# ManipulatorControlPartSCH.net
KiCad netlist of a schematic drawn in Altium Designer
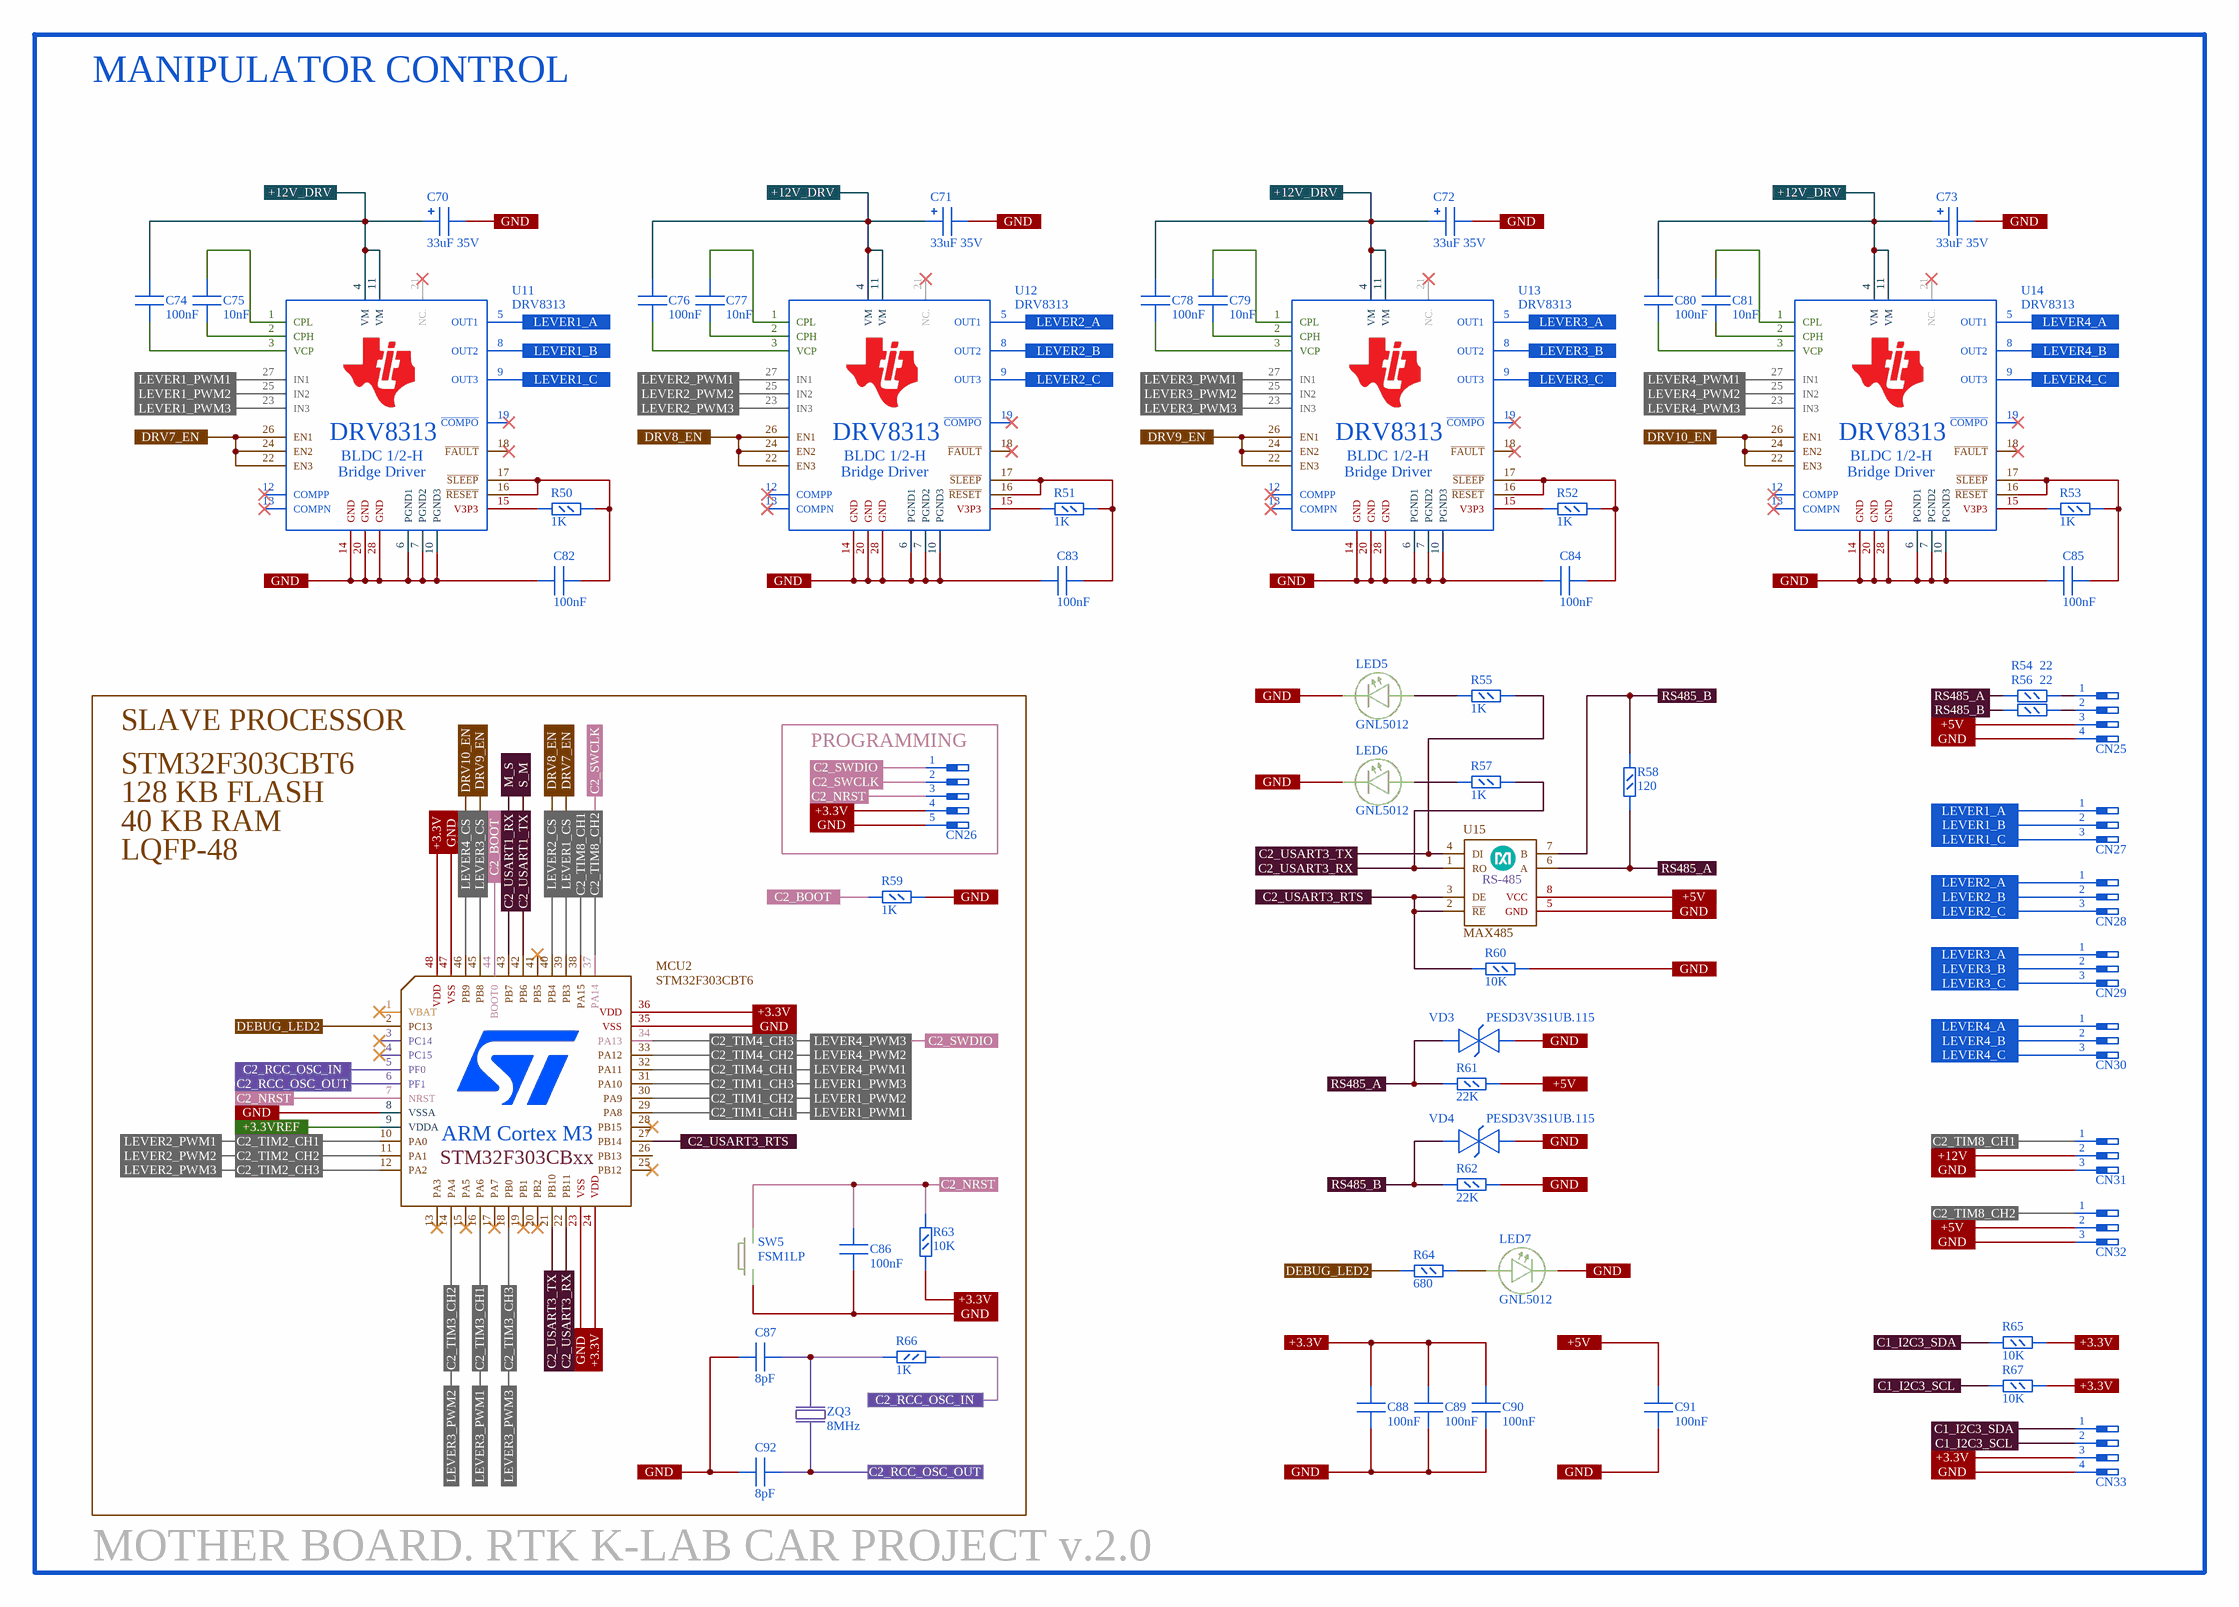
[diagram p0: ManipulatorControlPartSCH.SchDoc]

(export (version "E")
  (design (tool "Eeschema 10.0.6"))
  (components
    (comp (ref "C70")
      (value "33uF 35V")
      (footprint "CAP_TAN-B")
      (libsource (lib "CustomMillLib_Col") (part "Cap_Pol"))
    )
    (comp (ref "C71")
      (value "33uF 35V")
      (footprint "CAP_TAN-B")
      (libsource (lib "CustomMillLib_Col") (part "Cap_Pol"))
    )
    (comp (ref "C72")
      (value "33uF 35V")
      (footprint "CAP_TAN-B")
      (libsource (lib "CustomMillLib_Col") (part "Cap_Pol"))
    )
    (comp (ref "C73")
      (value "33uF 35V")
      (footprint "CAP_TAN-B")
      (libsource (lib "CustomMillLib_Col") (part "Cap_Pol"))
    )
    (comp (ref "C74") (value "100nF") (footprint "C0603") (libsource (lib "CommonElements") (part "Cap")))
    (comp (ref "C75") (value "10nF") (footprint "C0603") (libsource (lib "CommonElements") (part "Cap")))
    (comp (ref "C76") (value "100nF") (footprint "C0603") (libsource (lib "CommonElements") (part "Cap")))
    (comp (ref "C77") (value "10nF") (footprint "C0603") (libsource (lib "CommonElements") (part "Cap")))
    (comp (ref "C78") (value "100nF") (footprint "C0603") (libsource (lib "CommonElements") (part "Cap")))
    (comp (ref "C79") (value "10nF") (footprint "C0603") (libsource (lib "CommonElements") (part "Cap")))
    (comp (ref "C80") (value "100nF") (footprint "C0603") (libsource (lib "CommonElements") (part "Cap")))
    (comp (ref "C81") (value "10nF") (footprint "C0603") (libsource (lib "CommonElements") (part "Cap")))
    (comp (ref "C82") (value "100nF") (footprint "C0603") (libsource (lib "CommonElements") (part "Cap")))
    (comp (ref "C83") (value "100nF") (footprint "C0603") (libsource (lib "CommonElements") (part "Cap")))
    (comp (ref "C84") (value "100nF") (footprint "C0603") (libsource (lib "CommonElements") (part "Cap")))
    (comp (ref "C85") (value "100nF") (footprint "C0603") (libsource (lib "CommonElements") (part "Cap")))
    (comp (ref "C86") (value "100nF") (footprint "C0603") (libsource (lib "CommonElements") (part "Cap")))
    (comp (ref "C87") (value "8pF") (footprint "C0402") (libsource (lib "CommonElements") (part "Cap")))
    (comp (ref "C88") (value "100nF") (footprint "C0603") (libsource (lib "CommonElements") (part "Cap")))
    (comp (ref "C89") (value "100nF") (footprint "C0603") (libsource (lib "CommonElements") (part "Cap")))
    (comp (ref "C90") (value "100nF") (footprint "C0603") (libsource (lib "CommonElements") (part "Cap")))
    (comp (ref "C91") (value "100nF") (footprint "C0603") (libsource (lib "CommonElements") (part "Cap")))
    (comp (ref "C92") (value "8pF") (footprint "C0402") (libsource (lib "CommonElements") (part "Cap")))
    (comp (ref "CN25") (value "1x04") (footprint "XH2.54-4PIN") (libsource (lib "Connectors") (part "1x04")))
    (comp (ref "CN26") (value "1x05") (footprint "5X1M") (libsource (lib "Connectors") (part "1x05")))
    (comp (ref "CN27") (value "1x03") (footprint "H3-5.08") (libsource (lib "Connectors") (part "1x03")))
    (comp (ref "CN28") (value "1x03") (footprint "H3-5.08") (libsource (lib "Connectors") (part "1x03")))
    (comp (ref "CN29") (value "1x03") (footprint "H3-5.08") (libsource (lib "Connectors") (part "1x03")))
    (comp (ref "CN30") (value "1x03") (footprint "H3-5.08") (libsource (lib "Connectors") (part "1x03")))
    (comp (ref "CN31") (value "1x03") (footprint "3X1F-H8MM") (libsource (lib "Connectors") (part "1x03")))
    (comp (ref "CN32") (value "1x03") (footprint "3X1F-H8MM") (libsource (lib "Connectors") (part "1x03")))
    (comp (ref "CN33") (value "1x04") (footprint "XH2.54-4PIN") (libsource (lib "Connectors") (part "1x04")))
    (comp (ref "LED5")
      (value "GNL5012")
      (footprint "LED0603")
      (libsource (lib "CommonElements") (part "LED"))
    )
    (comp (ref "LED6")
      (value "GNL5012")
      (footprint "LED0603")
      (libsource (lib "CommonElements") (part "LED"))
    )
    (comp (ref "LED7")
      (value "GNL5012")
      (footprint "LED0603")
      (libsource (lib "CommonElements") (part "LED"))
    )
    (comp (ref "MCU2")
      (value "STM32F303CBT6")
      (footprint "LQFP48")
      (libsource (lib "STM32") (part "STM32F303CBxx"))
    )
    (comp (ref "R50") (value "1K") (footprint "R0603") (libsource (lib "CommonElements") (part "Res")))
    (comp (ref "R51") (value "1K") (footprint "R0603") (libsource (lib "CommonElements") (part "Res")))
    (comp (ref "R52") (value "1K") (footprint "R0603") (libsource (lib "CommonElements") (part "Res")))
    (comp (ref "R53") (value "1K") (footprint "R0603") (libsource (lib "CommonElements") (part "Res")))
    (comp (ref "R54") (value "22") (footprint "R0805") (libsource (lib "CommonElements") (part "Res")))
    (comp (ref "R55") (value "1K") (footprint "R0603") (libsource (lib "CommonElements") (part "Res")))
    (comp (ref "R56") (value "22") (footprint "R0805") (libsource (lib "CommonElements") (part "Res")))
    (comp (ref "R57") (value "1K") (footprint "R0603") (libsource (lib "CommonElements") (part "Res")))
    (comp (ref "R58") (value "120") (footprint "R0603") (libsource (lib "CommonElements") (part "Res")))
    (comp (ref "R59") (value "1K") (footprint "R0603") (libsource (lib "CommonElements") (part "Res")))
    (comp (ref "R60") (value "10K") (footprint "R0603") (libsource (lib "CommonElements") (part "Res")))
    (comp (ref "R61") (value "22K") (footprint "R0603") (libsource (lib "CommonElements") (part "Res")))
    (comp (ref "R62") (value "22K") (footprint "R0603") (libsource (lib "CommonElements") (part "Res")))
    (comp (ref "R63") (value "10K") (footprint "R0603") (libsource (lib "CommonElements") (part "Res")))
    (comp (ref "R64") (value "680") (footprint "R0603") (libsource (lib "CommonElements") (part "Res")))
    (comp (ref "R65") (value "10K") (footprint "R0603") (libsource (lib "CommonElements") (part "Res")))
    (comp (ref "R66") (value "1K") (footprint "R0603") (libsource (lib "CommonElements") (part "Res")))
    (comp (ref "R67") (value "10K") (footprint "R0603") (libsource (lib "CommonElements") (part "Res")))
    (comp (ref "SW5")
      (value "FSM1LP")
      (footprint "BUT-SMD-8X6.2MM")
      (libsource (lib "CommonElements") (part "Button"))
    )
    (comp (ref "U11")
      (value "DRV8313")
      (footprint "TSSOP28-TP")
      (libsource (lib "DigitalUnits") (part "DRV8313"))
    )
    (comp (ref "U12")
      (value "DRV8313")
      (footprint "TSSOP28-TP")
      (libsource (lib "DigitalUnits") (part "DRV8313"))
    )
    (comp (ref "U13")
      (value "DRV8313")
      (footprint "TSSOP28-TP")
      (libsource (lib "DigitalUnits") (part "DRV8313"))
    )
    (comp (ref "U14")
      (value "DRV8313")
      (footprint "TSSOP28-TP")
      (libsource (lib "DigitalUnits") (part "DRV8313"))
    )
    (comp (ref "U15")
      (value "MAX485")
      (footprint "SOIC8")
      (description "Driver RS-485")
      (libsource (lib "DigitalUnits") (part "MAX485"))
    )
    (comp (ref "VD3")
      (value "PESD3V3S1UB.115")
      (footprint "SOD-323")
      (libsource (lib "CommonElements") (part "Suppressor"))
    )
    (comp (ref "VD4")
      (value "PESD3V3S1UB.115")
      (footprint "SOD-323")
      (libsource (lib "CommonElements") (part "Suppressor"))
    )
    (comp (ref "ZQ3")
      (value "8MHz")
      (footprint "NX5032GA")
      (libsource (lib "CommonElements") (part "Crystall"))
    )
  )
  (nets
    (net (code "1") (name "/+3.3V") (class "Default")
      (node (ref "C88") (pin "2") (pinfunction "62_2") (pintype "passive"))
      (node (ref "C89") (pin "2") (pinfunction "62_2") (pintype "passive"))
      (node (ref "C90") (pin "2") (pinfunction "62_2") (pintype "passive"))
      (node (ref "CN26") (pin "4") (pintype "passive"))
      (node (ref "CN33") (pin "3") (pintype "passive"))
      (node (ref "MCU2") (pin "24") (pinfunction "VDD_24") (pintype "passive"))
      (node (ref "MCU2") (pin "36") (pinfunction "VDD_36") (pintype "passive"))
      (node (ref "MCU2") (pin "48") (pinfunction "VDD_48") (pintype "passive"))
      (node (ref "R63") (pin "2") (pinfunction "2_2") (pintype "passive"))
      (node (ref "R65") (pin "2") (pinfunction "2_2") (pintype "passive"))
      (node (ref "R67") (pin "2") (pinfunction "2_2") (pintype "passive"))
    )
    (net (code "2") (name "/+3.3VREF") (class "Default")
      (node (ref "MCU2") (pin "9") (pinfunction "VDDA_9") (pintype "passive"))
    )
    (net (code "3") (name "/+5V") (class "Default")
      (node (ref "C91") (pin "2") (pinfunction "62_2") (pintype "passive"))
      (node (ref "CN25") (pin "3") (pintype "passive"))
      (node (ref "CN32") (pin "2") (pintype "passive"))
      (node (ref "R61") (pin "1") (pinfunction "2_1") (pintype "passive"))
      (node (ref "U15") (pin "8") (pinfunction "VCC_8") (pintype "passive"))
    )
    (net (code "4") (name "/+12V") (class "Default") (node (ref "CN31") (pin "2") (pintype "passive")))
    (net (code "5") (name "/+12V_DRV") (class "Default")
      (node (ref "C70") (pin "1") (pinfunction "61_1") (pintype "passive"))
      (node (ref "C71") (pin "1") (pinfunction "61_1") (pintype "passive"))
      (node (ref "C72") (pin "1") (pinfunction "61_1") (pintype "passive"))
      (node (ref "C73") (pin "1") (pinfunction "61_1") (pintype "passive"))
      (node (ref "C74") (pin "2") (pinfunction "62_2") (pintype "passive"))
      (node (ref "C76") (pin "2") (pinfunction "62_2") (pintype "passive"))
      (node (ref "C78") (pin "2") (pinfunction "62_2") (pintype "passive"))
      (node (ref "C80") (pin "2") (pinfunction "62_2") (pintype "passive"))
      (node (ref "U11") (pin "11") (pinfunction "VM_11") (pintype "passive"))
      (node (ref "U11") (pin "4") (pinfunction "VM_4") (pintype "passive"))
      (node (ref "U12") (pin "11") (pinfunction "VM_11") (pintype "passive"))
      (node (ref "U12") (pin "4") (pinfunction "VM_4") (pintype "passive"))
      (node (ref "U13") (pin "11") (pinfunction "VM_11") (pintype "passive"))
      (node (ref "U13") (pin "4") (pinfunction "VM_4") (pintype "passive"))
      (node (ref "U14") (pin "11") (pinfunction "VM_11") (pintype "passive"))
      (node (ref "U14") (pin "4") (pinfunction "VM_4") (pintype "passive"))
    )
    (net (code "6") (name "/C1_I2C3_SCL") (class "Default")
      (node (ref "CN33") (pin "2") (pintype "passive"))
      (node (ref "R67") (pin "1") (pinfunction "2_1") (pintype "passive"))
    )
    (net (code "7") (name "/C1_I2C3_SDA") (class "Default")
      (node (ref "CN33") (pin "1") (pintype "passive"))
      (node (ref "R65") (pin "1") (pinfunction "2_1") (pintype "passive"))
    )
    (net (code "8") (name "/C2_BOOT") (class "Default")
      (node (ref "MCU2") (pin "44") (pinfunction "BOOT0_44") (pintype "passive"))
      (node (ref "R59") (pin "2") (pinfunction "2_2") (pintype "passive"))
    )
    (net (code "9") (name "/C2_NRST") (class "Default")
      (node (ref "C86") (pin "2") (pinfunction "62_2") (pintype "passive"))
      (node (ref "CN26") (pin "3") (pintype "passive"))
      (node (ref "MCU2") (pin "7") (pinfunction "NRST_7") (pintype "passive"))
      (node (ref "R63") (pin "1") (pinfunction "2_1") (pintype "passive"))
      (node (ref "SW5") (pin "3") (pinfunction "Q2_3") (pintype "passive"))
    )
    (net (code "10") (name "/C2_RCC_OSC_IN") (class "Default")
      (node (ref "MCU2") (pin "5") (pinfunction "PF0_5") (pintype "passive"))
      (node (ref "R66") (pin "1") (pinfunction "2_1") (pintype "passive"))
    )
    (net (code "11") (name "/C2_RCC_OSC_OUT") (class "Default")
      (node (ref "C92") (pin "1") (pinfunction "61_1") (pintype "passive"))
      (node (ref "MCU2") (pin "6") (pinfunction "PF1_6") (pintype "passive"))
      (node (ref "ZQ3") (pin "2") (pinfunction "2_2") (pintype "passive"))
    )
    (net (code "12") (name "/C2_SWCLK") (class "Default")
      (node (ref "CN26") (pin "2") (pintype "passive"))
      (node (ref "CN32") (pin "1") (pintype "passive"))
      (node (ref "MCU2") (pin "37") (pinfunction "PA14_37") (pintype "passive"))
    )
    (net (code "13") (name "/C2_SWDIO") (class "Default")
      (node (ref "CN26") (pin "1") (pintype "passive"))
      (node (ref "MCU2") (pin "34") (pinfunction "PA13_34") (pintype "passive"))
      (node (ref "U14") (pin "23") (pinfunction "IN3_23") (pintype "passive"))
    )
    (net (code "14") (name "/C2_TIM1_CH1") (class "Default")
      (node (ref "MCU2") (pin "29") (pinfunction "PA8_29") (pintype "passive"))
      (node (ref "U11") (pin "27") (pinfunction "IN1_27") (pintype "passive"))
    )
    (net (code "15") (name "/C2_TIM1_CH2") (class "Default")
      (node (ref "MCU2") (pin "30") (pinfunction "PA9_30") (pintype "passive"))
      (node (ref "U11") (pin "25") (pinfunction "IN2_25") (pintype "passive"))
    )
    (net (code "16") (name "/C2_TIM1_CH3") (class "Default")
      (node (ref "MCU2") (pin "31") (pinfunction "PA10_31") (pintype "passive"))
      (node (ref "U11") (pin "23") (pinfunction "IN3_23") (pintype "passive"))
    )
    (net (code "17") (name "/C2_TIM2_CH1") (class "Default")
      (node (ref "MCU2") (pin "10") (pinfunction "PA0_10") (pintype "passive"))
      (node (ref "U12") (pin "27") (pinfunction "IN1_27") (pintype "passive"))
    )
    (net (code "18") (name "/C2_TIM2_CH2") (class "Default")
      (node (ref "MCU2") (pin "11") (pinfunction "PA1_11") (pintype "passive"))
      (node (ref "U12") (pin "25") (pinfunction "IN2_25") (pintype "passive"))
    )
    (net (code "19") (name "/C2_TIM2_CH3") (class "Default")
      (node (ref "MCU2") (pin "12") (pinfunction "PA2_12") (pintype "passive"))
      (node (ref "U12") (pin "23") (pinfunction "IN3_23") (pintype "passive"))
    )
    (net (code "20") (name "/C2_TIM3_CH1") (class "Default")
      (node (ref "MCU2") (pin "16") (pinfunction "PA6_16") (pintype "passive"))
      (node (ref "U13") (pin "27") (pinfunction "IN1_27") (pintype "passive"))
    )
    (net (code "21") (name "/C2_TIM3_CH2") (class "Default")
      (node (ref "MCU2") (pin "14") (pinfunction "PA4_14") (pintype "passive"))
      (node (ref "U13") (pin "25") (pinfunction "IN2_25") (pintype "passive"))
    )
    (net (code "22") (name "/C2_TIM3_CH3") (class "Default")
      (node (ref "MCU2") (pin "18") (pinfunction "PB0_18") (pintype "passive"))
      (node (ref "U13") (pin "23") (pinfunction "IN3_23") (pintype "passive"))
    )
    (net (code "23") (name "/C2_TIM4_CH1") (class "Default")
      (node (ref "MCU2") (pin "32") (pinfunction "PA11_32") (pintype "passive"))
      (node (ref "U14") (pin "27") (pinfunction "IN1_27") (pintype "passive"))
    )
    (net (code "24") (name "/C2_TIM4_CH2") (class "Default")
      (node (ref "MCU2") (pin "33") (pinfunction "PA12_33") (pintype "passive"))
      (node (ref "U14") (pin "25") (pinfunction "IN2_25") (pintype "passive"))
    )
    (net (code "25") (name "/C2_TIM8_CH1") (class "Default")
      (node (ref "CN31") (pin "1") (pintype "passive"))
      (node (ref "MCU2") (pin "38") (pinfunction "PA15_38") (pintype "passive"))
    )
    (net (code "26") (name "/C2_USART1_RX") (class "Default")
      (node (ref "MCU2") (pin "43") (pinfunction "PB7_43") (pintype "passive"))
    )
    (net (code "27") (name "/C2_USART1_TX") (class "Default")
      (node (ref "MCU2") (pin "42") (pinfunction "PB6_42") (pintype "passive"))
    )
    (net (code "28") (name "/C2_USART3_RTS") (class "Default")
      (node (ref "MCU2") (pin "27") (pinfunction "PB14_27") (pintype "passive"))
      (node (ref "R60") (pin "2") (pinfunction "2_2") (pintype "passive"))
      (node (ref "U15") (pin "2") (pinfunction "RE_2") (pintype "passive"))
      (node (ref "U15") (pin "3") (pinfunction "DE_3") (pintype "passive"))
    )
    (net (code "29") (name "/C2_USART3_RX") (class "Default")
      (node (ref "MCU2") (pin "22") (pinfunction "PB11_22") (pintype "passive"))
      (node (ref "R57") (pin "1") (pinfunction "2_1") (pintype "passive"))
      (node (ref "U15") (pin "1") (pinfunction "RO_1") (pintype "passive"))
    )
    (net (code "30") (name "/C2_USART3_TX") (class "Default")
      (node (ref "MCU2") (pin "21") (pinfunction "PB10_21") (pintype "passive"))
      (node (ref "R55") (pin "1") (pinfunction "2_1") (pintype "passive"))
      (node (ref "U15") (pin "4") (pinfunction "DI_4") (pintype "passive"))
    )
    (net (code "31") (name "/DEBUG_LED2") (class "Default")
      (node (ref "MCU2") (pin "2") (pinfunction "PC13_2") (pintype "passive"))
      (node (ref "R64") (pin "2") (pinfunction "2_2") (pintype "passive"))
    )
    (net (code "32") (name "/DRV7_EN") (class "Default")
      (node (ref "MCU2") (pin "39") (pinfunction "PB3_39") (pintype "passive"))
      (node (ref "U11") (pin "22") (pinfunction "EN3_22") (pintype "passive"))
      (node (ref "U11") (pin "24") (pinfunction "EN2_24") (pintype "passive"))
      (node (ref "U11") (pin "26") (pinfunction "EN1_26") (pintype "passive"))
    )
    (net (code "33") (name "/DRV8_EN") (class "Default")
      (node (ref "MCU2") (pin "40") (pinfunction "PB4_40") (pintype "passive"))
      (node (ref "U12") (pin "22") (pinfunction "EN3_22") (pintype "passive"))
      (node (ref "U12") (pin "24") (pinfunction "EN2_24") (pintype "passive"))
      (node (ref "U12") (pin "26") (pinfunction "EN1_26") (pintype "passive"))
    )
    (net (code "34") (name "/DRV9_EN") (class "Default")
      (node (ref "MCU2") (pin "45") (pinfunction "PB8_45") (pintype "passive"))
      (node (ref "U13") (pin "22") (pinfunction "EN3_22") (pintype "passive"))
      (node (ref "U13") (pin "24") (pinfunction "EN2_24") (pintype "passive"))
      (node (ref "U13") (pin "26") (pinfunction "EN1_26") (pintype "passive"))
    )
    (net (code "35") (name "/DRV10_EN") (class "Default")
      (node (ref "MCU2") (pin "46") (pinfunction "PB9_46") (pintype "passive"))
      (node (ref "U14") (pin "22") (pinfunction "EN3_22") (pintype "passive"))
      (node (ref "U14") (pin "24") (pinfunction "EN2_24") (pintype "passive"))
      (node (ref "U14") (pin "26") (pinfunction "EN1_26") (pintype "passive"))
    )
    (net (code "36") (name "/GND") (class "Default")
      (node (ref "C70") (pin "2") (pinfunction "62_2") (pintype "passive"))
      (node (ref "C71") (pin "2") (pinfunction "62_2") (pintype "passive"))
      (node (ref "C72") (pin "2") (pinfunction "62_2") (pintype "passive"))
      (node (ref "C73") (pin "2") (pinfunction "62_2") (pintype "passive"))
      (node (ref "C82") (pin "1") (pinfunction "61_1") (pintype "passive"))
      (node (ref "C83") (pin "1") (pinfunction "61_1") (pintype "passive"))
      (node (ref "C84") (pin "1") (pinfunction "61_1") (pintype "passive"))
      (node (ref "C85") (pin "1") (pinfunction "61_1") (pintype "passive"))
      (node (ref "C86") (pin "1") (pinfunction "61_1") (pintype "passive"))
      (node (ref "C87") (pin "2") (pinfunction "62_2") (pintype "passive"))
      (node (ref "C88") (pin "1") (pinfunction "61_1") (pintype "passive"))
      (node (ref "C89") (pin "1") (pinfunction "61_1") (pintype "passive"))
      (node (ref "C90") (pin "1") (pinfunction "61_1") (pintype "passive"))
      (node (ref "C91") (pin "1") (pinfunction "61_1") (pintype "passive"))
      (node (ref "C92") (pin "2") (pinfunction "62_2") (pintype "passive"))
      (node (ref "CN25") (pin "4") (pintype "passive"))
      (node (ref "CN26") (pin "5") (pintype "passive"))
      (node (ref "CN31") (pin "3") (pintype "passive"))
      (node (ref "CN32") (pin "3") (pintype "passive"))
      (node (ref "CN33") (pin "4") (pintype "passive"))
      (node (ref "LED5") (pin "2") (pinfunction "6_2") (pintype "passive"))
      (node (ref "LED6") (pin "2") (pinfunction "6_2") (pintype "passive"))
      (node (ref "LED7") (pin "2") (pinfunction "6_2") (pintype "passive"))
      (node (ref "MCU2") (pin "23") (pinfunction "VSS_23") (pintype "passive"))
      (node (ref "MCU2") (pin "35") (pinfunction "VSS_35") (pintype "passive"))
      (node (ref "MCU2") (pin "47") (pinfunction "VSS_47") (pintype "passive"))
      (node (ref "MCU2") (pin "8") (pinfunction "VSSA_8") (pintype "passive"))
      (node (ref "R59") (pin "1") (pinfunction "2_1") (pintype "passive"))
      (node (ref "R60") (pin "1") (pinfunction "2_1") (pintype "passive"))
      (node (ref "R62") (pin "1") (pinfunction "2_1") (pintype "passive"))
      (node (ref "SW5") (pin "1") (pinfunction "Q1_1") (pintype "passive"))
      (node (ref "U11") (pin "10") (pinfunction "PGND3_10") (pintype "passive"))
      (node (ref "U11") (pin "14") (pinfunction "GND_14") (pintype "passive"))
      (node (ref "U11") (pin "20") (pinfunction "GND_20") (pintype "passive"))
      (node (ref "U11") (pin "28") (pinfunction "GND_28") (pintype "passive"))
      (node (ref "U11") (pin "6") (pinfunction "PGND1_6") (pintype "passive"))
      (node (ref "U11") (pin "7") (pinfunction "PGND2_7") (pintype "passive"))
      (node (ref "U12") (pin "10") (pinfunction "PGND3_10") (pintype "passive"))
      (node (ref "U12") (pin "14") (pinfunction "GND_14") (pintype "passive"))
      (node (ref "U12") (pin "20") (pinfunction "GND_20") (pintype "passive"))
      (node (ref "U12") (pin "28") (pinfunction "GND_28") (pintype "passive"))
      (node (ref "U12") (pin "6") (pinfunction "PGND1_6") (pintype "passive"))
      (node (ref "U12") (pin "7") (pinfunction "PGND2_7") (pintype "passive"))
      (node (ref "U13") (pin "10") (pinfunction "PGND3_10") (pintype "passive"))
      (node (ref "U13") (pin "14") (pinfunction "GND_14") (pintype "passive"))
      (node (ref "U13") (pin "20") (pinfunction "GND_20") (pintype "passive"))
      (node (ref "U13") (pin "28") (pinfunction "GND_28") (pintype "passive"))
      (node (ref "U13") (pin "6") (pinfunction "PGND1_6") (pintype "passive"))
      (node (ref "U13") (pin "7") (pinfunction "PGND2_7") (pintype "passive"))
      (node (ref "U14") (pin "10") (pinfunction "PGND3_10") (pintype "passive"))
      (node (ref "U14") (pin "14") (pinfunction "GND_14") (pintype "passive"))
      (node (ref "U14") (pin "20") (pinfunction "GND_20") (pintype "passive"))
      (node (ref "U14") (pin "28") (pinfunction "GND_28") (pintype "passive"))
      (node (ref "U14") (pin "6") (pinfunction "PGND1_6") (pintype "passive"))
      (node (ref "U14") (pin "7") (pinfunction "PGND2_7") (pintype "passive"))
      (node (ref "U15") (pin "5") (pinfunction "GND_5") (pintype "passive"))
      (node (ref "VD3") (pin "2") (pinfunction "64_2") (pintype "passive"))
      (node (ref "VD4") (pin "2") (pinfunction "64_2") (pintype "passive"))
    )
    (net (code "37") (name "/LEVER1_A") (class "Default")
      (node (ref "CN27") (pin "1") (pintype "passive"))
      (node (ref "U11") (pin "5") (pinfunction "OUT1_5") (pintype "passive"))
    )
    (net (code "38") (name "/LEVER1_B") (class "Default")
      (node (ref "CN27") (pin "2") (pintype "passive"))
      (node (ref "U11") (pin "8") (pinfunction "OUT2_8") (pintype "passive"))
    )
    (net (code "39") (name "/LEVER1_C") (class "Default")
      (node (ref "CN27") (pin "3") (pintype "passive"))
      (node (ref "U11") (pin "9") (pinfunction "OUT3_9") (pintype "passive"))
    )
    (net (code "40") (name "/LEVER2_A") (class "Default")
      (node (ref "CN28") (pin "1") (pintype "passive"))
      (node (ref "U12") (pin "5") (pinfunction "OUT1_5") (pintype "passive"))
    )
    (net (code "41") (name "/LEVER2_B") (class "Default")
      (node (ref "CN28") (pin "2") (pintype "passive"))
      (node (ref "U12") (pin "8") (pinfunction "OUT2_8") (pintype "passive"))
    )
    (net (code "42") (name "/LEVER2_C") (class "Default")
      (node (ref "CN28") (pin "3") (pintype "passive"))
      (node (ref "U12") (pin "9") (pinfunction "OUT3_9") (pintype "passive"))
    )
    (net (code "43") (name "/LEVER3_A") (class "Default")
      (node (ref "CN29") (pin "1") (pintype "passive"))
      (node (ref "U13") (pin "5") (pinfunction "OUT1_5") (pintype "passive"))
    )
    (net (code "44") (name "/LEVER3_B") (class "Default")
      (node (ref "CN29") (pin "2") (pintype "passive"))
      (node (ref "U13") (pin "8") (pinfunction "OUT2_8") (pintype "passive"))
    )
    (net (code "45") (name "/LEVER3_C") (class "Default")
      (node (ref "CN29") (pin "3") (pintype "passive"))
      (node (ref "U13") (pin "9") (pinfunction "OUT3_9") (pintype "passive"))
    )
    (net (code "46") (name "/LEVER4_A") (class "Default")
      (node (ref "CN30") (pin "1") (pintype "passive"))
      (node (ref "U14") (pin "5") (pinfunction "OUT1_5") (pintype "passive"))
    )
    (net (code "47") (name "/LEVER4_B") (class "Default")
      (node (ref "CN30") (pin "2") (pintype "passive"))
      (node (ref "U14") (pin "8") (pinfunction "OUT2_8") (pintype "passive"))
    )
    (net (code "48") (name "/LEVER4_C") (class "Default")
      (node (ref "CN30") (pin "3") (pintype "passive"))
      (node (ref "U14") (pin "9") (pinfunction "OUT3_9") (pintype "passive"))
    )
    (net (code "49") (name "/RS485_A") (class "Default")
      (node (ref "R54") (pin "2") (pinfunction "2_2") (pintype "passive"))
      (node (ref "R58") (pin "1") (pinfunction "2_1") (pintype "passive"))
      (node (ref "R61") (pin "2") (pinfunction "2_2") (pintype "passive"))
      (node (ref "U15") (pin "6") (pinfunction "A_6") (pintype "passive"))
      (node (ref "VD3") (pin "1") (pinfunction "63_1") (pintype "passive"))
    )
    (net (code "50") (name "/RS485_B") (class "Default")
      (node (ref "R56") (pin "2") (pinfunction "2_2") (pintype "passive"))
      (node (ref "R58") (pin "2") (pinfunction "2_2") (pintype "passive"))
      (node (ref "R62") (pin "2") (pinfunction "2_2") (pintype "passive"))
      (node (ref "U15") (pin "7") (pinfunction "B_7") (pintype "passive"))
      (node (ref "VD4") (pin "1") (pinfunction "63_1") (pintype "passive"))
    )
    (net (code "51") (name "Net-(C74-61)") (class "Default")
      (node (ref "C74") (pin "1") (pinfunction "61_1") (pintype "passive"))
      (node (ref "U11") (pin "3") (pinfunction "VCP_3") (pintype "passive"))
    )
    (net (code "52") (name "Net-(C75-61)") (class "Default")
      (node (ref "C75") (pin "1") (pinfunction "61_1") (pintype "passive"))
      (node (ref "U11") (pin "2") (pinfunction "CPH_2") (pintype "passive"))
    )
    (net (code "53") (name "Net-(C75-62)") (class "Default")
      (node (ref "C75") (pin "2") (pinfunction "62_2") (pintype "passive"))
      (node (ref "U11") (pin "1") (pinfunction "CPL_1") (pintype "passive"))
    )
    (net (code "54") (name "Net-(C76-61)") (class "Default")
      (node (ref "C76") (pin "1") (pinfunction "61_1") (pintype "passive"))
      (node (ref "U12") (pin "3") (pinfunction "VCP_3") (pintype "passive"))
    )
    (net (code "55") (name "Net-(C77-61)") (class "Default")
      (node (ref "C77") (pin "1") (pinfunction "61_1") (pintype "passive"))
      (node (ref "U12") (pin "2") (pinfunction "CPH_2") (pintype "passive"))
    )
    (net (code "56") (name "Net-(C77-62)") (class "Default")
      (node (ref "C77") (pin "2") (pinfunction "62_2") (pintype "passive"))
      (node (ref "U12") (pin "1") (pinfunction "CPL_1") (pintype "passive"))
    )
    (net (code "57") (name "Net-(C78-61)") (class "Default")
      (node (ref "C78") (pin "1") (pinfunction "61_1") (pintype "passive"))
      (node (ref "U13") (pin "3") (pinfunction "VCP_3") (pintype "passive"))
    )
    (net (code "58") (name "Net-(C79-61)") (class "Default")
      (node (ref "C79") (pin "1") (pinfunction "61_1") (pintype "passive"))
      (node (ref "U13") (pin "2") (pinfunction "CPH_2") (pintype "passive"))
    )
    (net (code "59") (name "Net-(C79-62)") (class "Default")
      (node (ref "C79") (pin "2") (pinfunction "62_2") (pintype "passive"))
      (node (ref "U13") (pin "1") (pinfunction "CPL_1") (pintype "passive"))
    )
    (net (code "60") (name "Net-(C80-61)") (class "Default")
      (node (ref "C80") (pin "1") (pinfunction "61_1") (pintype "passive"))
      (node (ref "U14") (pin "3") (pinfunction "VCP_3") (pintype "passive"))
    )
    (net (code "61") (name "Net-(C81-61)") (class "Default")
      (node (ref "C81") (pin "1") (pinfunction "61_1") (pintype "passive"))
      (node (ref "U14") (pin "2") (pinfunction "CPH_2") (pintype "passive"))
    )
    (net (code "62") (name "Net-(C81-62)") (class "Default")
      (node (ref "C81") (pin "2") (pinfunction "62_2") (pintype "passive"))
      (node (ref "U14") (pin "1") (pinfunction "CPL_1") (pintype "passive"))
    )
    (net (code "63") (name "Net-(C82-62)") (class "Default")
      (node (ref "C82") (pin "2") (pinfunction "62_2") (pintype "passive"))
      (node (ref "R50") (pin "2") (pinfunction "2_2") (pintype "passive"))
      (node (ref "U11") (pin "16") (pinfunction "RESET_16") (pintype "passive"))
      (node (ref "U11") (pin "17") (pinfunction "SLEEP_17") (pintype "passive"))
    )
    (net (code "64") (name "Net-(C83-62)") (class "Default")
      (node (ref "C83") (pin "2") (pinfunction "62_2") (pintype "passive"))
      (node (ref "R51") (pin "2") (pinfunction "2_2") (pintype "passive"))
      (node (ref "U12") (pin "16") (pinfunction "RESET_16") (pintype "passive"))
      (node (ref "U12") (pin "17") (pinfunction "SLEEP_17") (pintype "passive"))
    )
    (net (code "65") (name "Net-(C84-62)") (class "Default")
      (node (ref "C84") (pin "2") (pinfunction "62_2") (pintype "passive"))
      (node (ref "R52") (pin "2") (pinfunction "2_2") (pintype "passive"))
      (node (ref "U13") (pin "16") (pinfunction "RESET_16") (pintype "passive"))
      (node (ref "U13") (pin "17") (pinfunction "SLEEP_17") (pintype "passive"))
    )
    (net (code "66") (name "Net-(C85-62)") (class "Default")
      (node (ref "C85") (pin "2") (pinfunction "62_2") (pintype "passive"))
      (node (ref "R53") (pin "2") (pinfunction "2_2") (pintype "passive"))
      (node (ref "U14") (pin "16") (pinfunction "RESET_16") (pintype "passive"))
      (node (ref "U14") (pin "17") (pinfunction "SLEEP_17") (pintype "passive"))
    )
    (net (code "67") (name "Net-(C87-61)") (class "Default")
      (node (ref "C87") (pin "1") (pinfunction "61_1") (pintype "passive"))
      (node (ref "R66") (pin "2") (pinfunction "2_2") (pintype "passive"))
      (node (ref "ZQ3") (pin "1") (pinfunction "10_1") (pintype "passive"))
    )
    (net (code "68") (name "Net-(CN25-Pad1)") (class "Default")
      (node (ref "CN25") (pin "1") (pintype "passive"))
      (node (ref "R54") (pin "1") (pinfunction "2_1") (pintype "passive"))
    )
    (net (code "69") (name "Net-(CN25-Pad2)") (class "Default")
      (node (ref "CN25") (pin "2") (pintype "passive"))
      (node (ref "R56") (pin "1") (pinfunction "2_1") (pintype "passive"))
    )
    (net (code "70") (name "Net-(LED5-5)") (class "Default")
      (node (ref "LED5") (pin "1") (pinfunction "5_1") (pintype "passive"))
      (node (ref "R55") (pin "2") (pinfunction "2_2") (pintype "passive"))
    )
    (net (code "71") (name "Net-(LED6-5)") (class "Default")
      (node (ref "LED6") (pin "1") (pinfunction "5_1") (pintype "passive"))
      (node (ref "R57") (pin "2") (pinfunction "2_2") (pintype "passive"))
    )
    (net (code "72") (name "Net-(LED7-5)") (class "Default")
      (node (ref "LED7") (pin "1") (pinfunction "5_1") (pintype "passive"))
      (node (ref "R64") (pin "1") (pinfunction "2_1") (pintype "passive"))
    )
    (net (code "73") (name "Net-(U11-V3P3)") (class "Default")
      (node (ref "R50") (pin "1") (pinfunction "2_1") (pintype "passive"))
      (node (ref "U11") (pin "15") (pinfunction "V3P3_15") (pintype "passive"))
    )
    (net (code "74") (name "Net-(U12-V3P3)") (class "Default")
      (node (ref "R51") (pin "1") (pinfunction "2_1") (pintype "passive"))
      (node (ref "U12") (pin "15") (pinfunction "V3P3_15") (pintype "passive"))
    )
    (net (code "75") (name "Net-(U13-V3P3)") (class "Default")
      (node (ref "R52") (pin "1") (pinfunction "2_1") (pintype "passive"))
      (node (ref "U13") (pin "15") (pinfunction "V3P3_15") (pintype "passive"))
    )
    (net (code "76") (name "Net-(U14-V3P3)") (class "Default")
      (node (ref "R53") (pin "1") (pinfunction "2_1") (pintype "passive"))
      (node (ref "U14") (pin "15") (pinfunction "V3P3_15") (pintype "passive"))
    )
    (net (code "77") (name "unconnected-(MCU2-PA3-Pad13)") (class "Default")
      (node (ref "MCU2") (pin "13") (pinfunction "PA3_13") (pintype "passive+no_connect"))
    )
    (net (code "78") (name "unconnected-(MCU2-PA5-Pad15)") (class "Default")
      (node (ref "MCU2") (pin "15") (pinfunction "PA5_15") (pintype "passive+no_connect"))
    )
    (net (code "79") (name "unconnected-(MCU2-PA7-Pad17)") (class "Default")
      (node (ref "MCU2") (pin "17") (pinfunction "PA7_17") (pintype "passive+no_connect"))
    )
    (net (code "80") (name "unconnected-(MCU2-PB1-Pad19)") (class "Default")
      (node (ref "MCU2") (pin "19") (pinfunction "PB1_19") (pintype "passive+no_connect"))
    )
    (net (code "81") (name "unconnected-(MCU2-PB2-Pad20)") (class "Default")
      (node (ref "MCU2") (pin "20") (pinfunction "PB2_20") (pintype "passive+no_connect"))
    )
    (net (code "82") (name "unconnected-(MCU2-PB5-Pad41)") (class "Default")
      (node (ref "MCU2") (pin "41") (pinfunction "PB5_41") (pintype "passive+no_connect"))
    )
    (net (code "83") (name "unconnected-(MCU2-PB12-Pad25)") (class "Default")
      (node (ref "MCU2") (pin "25") (pinfunction "PB12_25") (pintype "passive+no_connect"))
    )
    (net (code "84") (name "unconnected-(MCU2-PB13-Pad26)") (class "Default")
      (node (ref "MCU2") (pin "26") (pinfunction "PB13_26") (pintype "passive"))
    )
    (net (code "85") (name "unconnected-(MCU2-PB15-Pad28)") (class "Default")
      (node (ref "MCU2") (pin "28") (pinfunction "PB15_28") (pintype "passive+no_connect"))
    )
    (net (code "86") (name "unconnected-(MCU2-PC14-Pad3)") (class "Default")
      (node (ref "MCU2") (pin "3") (pinfunction "PC14_3") (pintype "passive+no_connect"))
    )
    (net (code "87") (name "unconnected-(MCU2-PC15-Pad4)") (class "Default")
      (node (ref "MCU2") (pin "4") (pinfunction "PC15_4") (pintype "passive+no_connect"))
    )
    (net (code "88") (name "unconnected-(MCU2-VBAT-Pad1)") (class "Default")
      (node (ref "MCU2") (pin "1") (pinfunction "VBAT_1") (pintype "passive+no_connect"))
    )
    (net (code "89") (name "unconnected-(SW5-Q1-Pad2)") (class "Default")
      (node (ref "SW5") (pin "2") (pinfunction "Q1_2") (pintype "passive"))
    )
    (net (code "90") (name "unconnected-(SW5-Q2-Pad4)") (class "Default")
      (node (ref "SW5") (pin "4") (pinfunction "Q2_4") (pintype "passive"))
    )
    (net (code "91") (name "unconnected-(U11-COMPN-Pad13)") (class "Default")
      (node (ref "U11") (pin "13") (pinfunction "COMPN_13") (pintype "passive+no_connect"))
    )
    (net (code "92") (name "unconnected-(U11-COMPO-Pad19)") (class "Default")
      (node (ref "U11") (pin "19") (pinfunction "COMPO_19") (pintype "passive+no_connect"))
    )
    (net (code "93") (name "unconnected-(U11-COMPP-Pad12)") (class "Default")
      (node (ref "U11") (pin "12") (pinfunction "COMPP_12") (pintype "passive+no_connect"))
    )
    (net (code "94") (name "unconnected-(U11-FAULT-Pad18)") (class "Default")
      (node (ref "U11") (pin "18") (pinfunction "FAULT_18") (pintype "passive+no_connect"))
    )
    (net (code "95") (name "unconnected-(U11-NC.-Pad21)") (class "Default")
      (node (ref "U11") (pin "21") (pinfunction "NC._21") (pintype "passive+no_connect"))
    )
    (net (code "96") (name "unconnected-(U12-COMPN-Pad13)") (class "Default")
      (node (ref "U12") (pin "13") (pinfunction "COMPN_13") (pintype "passive+no_connect"))
    )
    (net (code "97") (name "unconnected-(U12-COMPO-Pad19)") (class "Default")
      (node (ref "U12") (pin "19") (pinfunction "COMPO_19") (pintype "passive+no_connect"))
    )
    (net (code "98") (name "unconnected-(U12-COMPP-Pad12)") (class "Default")
      (node (ref "U12") (pin "12") (pinfunction "COMPP_12") (pintype "passive+no_connect"))
    )
    (net (code "99") (name "unconnected-(U12-FAULT-Pad18)") (class "Default")
      (node (ref "U12") (pin "18") (pinfunction "FAULT_18") (pintype "passive+no_connect"))
    )
    (net (code "100") (name "unconnected-(U12-NC.-Pad21)") (class "Default")
      (node (ref "U12") (pin "21") (pinfunction "NC._21") (pintype "passive+no_connect"))
    )
    (net (code "101") (name "unconnected-(U13-COMPN-Pad13)") (class "Default")
      (node (ref "U13") (pin "13") (pinfunction "COMPN_13") (pintype "passive+no_connect"))
    )
    (net (code "102") (name "unconnected-(U13-COMPO-Pad19)") (class "Default")
      (node (ref "U13") (pin "19") (pinfunction "COMPO_19") (pintype "passive+no_connect"))
    )
    (net (code "103") (name "unconnected-(U13-COMPP-Pad12)") (class "Default")
      (node (ref "U13") (pin "12") (pinfunction "COMPP_12") (pintype "passive+no_connect"))
    )
    (net (code "104") (name "unconnected-(U13-FAULT-Pad18)") (class "Default")
      (node (ref "U13") (pin "18") (pinfunction "FAULT_18") (pintype "passive+no_connect"))
    )
    (net (code "105") (name "unconnected-(U13-NC.-Pad21)") (class "Default")
      (node (ref "U13") (pin "21") (pinfunction "NC._21") (pintype "passive+no_connect"))
    )
    (net (code "106") (name "unconnected-(U14-COMPN-Pad13)") (class "Default")
      (node (ref "U14") (pin "13") (pinfunction "COMPN_13") (pintype "passive+no_connect"))
    )
    (net (code "107") (name "unconnected-(U14-COMPO-Pad19)") (class "Default")
      (node (ref "U14") (pin "19") (pinfunction "COMPO_19") (pintype "passive+no_connect"))
    )
    (net (code "108") (name "unconnected-(U14-COMPP-Pad12)") (class "Default")
      (node (ref "U14") (pin "12") (pinfunction "COMPP_12") (pintype "passive+no_connect"))
    )
    (net (code "109") (name "unconnected-(U14-FAULT-Pad18)") (class "Default")
      (node (ref "U14") (pin "18") (pinfunction "FAULT_18") (pintype "passive+no_connect"))
    )
    (net (code "110") (name "unconnected-(U14-NC.-Pad21)") (class "Default")
      (node (ref "U14") (pin "21") (pinfunction "NC._21") (pintype "passive+no_connect"))
    )
  )
)
